# 05_FPGA_HVIO.net
KiCad netlist of a schematic drawn in Altium Designer
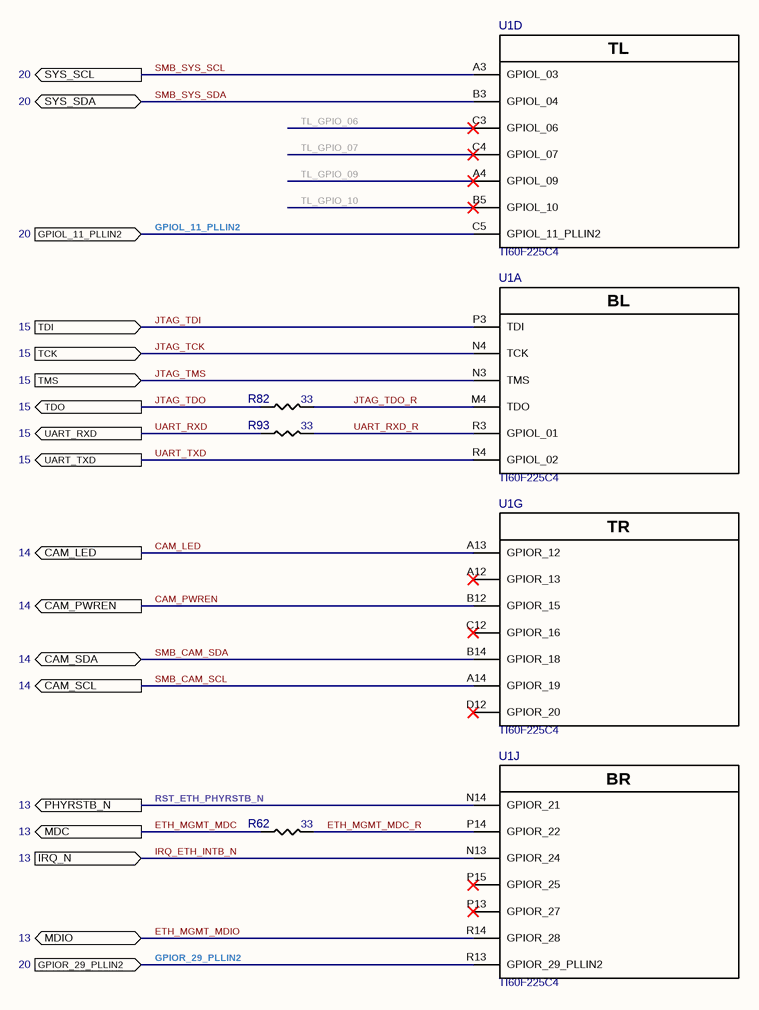
[diagram p0: 05_FPGA_HVIO.SchDoc]

(export (version "E")
  (design (tool "Eeschema 10.0.6"))
  (components
    (comp (ref "R62")
      (value "33")
      (footprint "RESC1005X03N")
      (description "RES SMD 33 OHM 1% 1/16W 0402")
      (fields (field (name "PART NUMBER") "RC0402FR-0733RL"))
      (libsource (lib "Database") (part "Resistor_ENG"))
    )
    (comp (ref "R82")
      (value "33")
      (footprint "RESC1005X03N")
      (description "RES SMD 33 OHM 1% 1/16W 0402")
      (fields (field (name "PART NUMBER") "RC0402FR-0733RL"))
      (libsource (lib "Database") (part "Resistor_ENG"))
    )
    (comp (ref "R93")
      (value "33")
      (footprint "RESC1005X03N")
      (description "RES SMD 33 OHM 1% 1/16W 0402")
      (fields (field (name "PART NUMBER") "RC0402FR-0733RL"))
      (libsource (lib "Database") (part "Resistor_ENG"))
    )
    (comp (ref "U1")
      (value "TI60F225C4")
      (footprint "BGA225C65P15X15_1000X1000X100")
      (description "FPGA TITAN 140HSIO 4PLL 225BGA")
      (libsource (lib "Database") (part "TI60F225"))
    )
  )
  (nets
    (net (code "1") (name "/CAM_LED") (class "Default")
      (node (ref "U1") (pin "A13") (pinfunction "GPIOR_12_A13") (pintype "passive"))
    )
    (net (code "2") (name "/CAM_PWREN") (class "Default")
      (node (ref "U1") (pin "B12") (pinfunction "GPIOR_15_B12") (pintype "passive"))
    )
    (net (code "3") (name "/ETH_MGMT_MDC") (class "Default")
      (node (ref "R62") (pin "1") (pinfunction "1_1") (pintype "passive"))
    )
    (net (code "4") (name "/ETH_MGMT_MDC_R") (class "Default")
      (node (ref "R62") (pin "2") (pinfunction "2_2") (pintype "passive"))
      (node (ref "U1") (pin "P14") (pinfunction "GPIOR_22_P14") (pintype "passive"))
    )
    (net (code "5") (name "/ETH_MGMT_MDIO") (class "Default")
      (node (ref "U1") (pin "R14") (pinfunction "GPIOR_28_R14") (pintype "passive"))
    )
    (net (code "6") (name "/GPIOL_11_PLLIN2") (class "Default")
      (node (ref "U1") (pin "C5") (pinfunction "GPIOL_11_PLLIN2_C5") (pintype "passive"))
    )
    (net (code "7") (name "/GPIOR_29_PLLIN2") (class "Default")
      (node (ref "U1") (pin "R13") (pinfunction "GPIOR_29_PLLIN2_R13") (pintype "passive"))
    )
    (net (code "8") (name "/IRQ_ETH_INTB_N") (class "Default")
      (node (ref "U1") (pin "N13") (pinfunction "GPIOR_24_N13") (pintype "passive"))
    )
    (net (code "9") (name "/JTAG_TCK") (class "Default")
      (node (ref "U1") (pin "N4") (pinfunction "TCK_N4") (pintype "passive"))
    )
    (net (code "10") (name "/JTAG_TDI") (class "Default")
      (node (ref "U1") (pin "P3") (pinfunction "TDI_P3") (pintype "passive"))
    )
    (net (code "11") (name "/JTAG_TDO") (class "Default")
      (node (ref "R82") (pin "1") (pinfunction "1_1") (pintype "passive"))
    )
    (net (code "12") (name "/JTAG_TDO_R") (class "Default")
      (node (ref "R82") (pin "2") (pinfunction "2_2") (pintype "passive"))
      (node (ref "U1") (pin "M4") (pinfunction "TDO_M4") (pintype "passive"))
    )
    (net (code "13") (name "/JTAG_TMS") (class "Default")
      (node (ref "U1") (pin "N3") (pinfunction "TMS_N3") (pintype "passive"))
    )
    (net (code "14") (name "/RST_ETH_PHYRSTB_N") (class "Default")
      (node (ref "U1") (pin "N14") (pinfunction "GPIOR_21_N14") (pintype "passive"))
    )
    (net (code "15") (name "/SMB_CAM_SCL") (class "Default")
      (node (ref "U1") (pin "A14") (pinfunction "GPIOR_19_A14") (pintype "passive"))
    )
    (net (code "16") (name "/SMB_CAM_SDA") (class "Default")
      (node (ref "U1") (pin "B14") (pinfunction "GPIOR_18_B14") (pintype "passive"))
    )
    (net (code "17") (name "/SMB_SYS_SCL") (class "Default")
      (node (ref "U1") (pin "A3") (pinfunction "GPIOL_03_A3") (pintype "passive"))
    )
    (net (code "18") (name "/SMB_SYS_SDA") (class "Default")
      (node (ref "U1") (pin "B3") (pinfunction "GPIOL_04_B3") (pintype "passive"))
    )
    (net (code "19") (name "/TL_GPIO_06") (class "Default")
      (node (ref "U1") (pin "C3") (pinfunction "GPIOL_06_C3") (pintype "passive+no_connect"))
    )
    (net (code "20") (name "/TL_GPIO_07") (class "Default")
      (node (ref "U1") (pin "C4") (pinfunction "GPIOL_07_C4") (pintype "passive+no_connect"))
    )
    (net (code "21") (name "/TL_GPIO_09") (class "Default")
      (node (ref "U1") (pin "A4") (pinfunction "GPIOL_09_A4") (pintype "passive+no_connect"))
    )
    (net (code "22") (name "/TL_GPIO_10") (class "Default")
      (node (ref "U1") (pin "B5") (pinfunction "GPIOL_10_B5") (pintype "passive+no_connect"))
    )
    (net (code "23") (name "/UART_RXD") (class "Default")
      (node (ref "R93") (pin "1") (pinfunction "1_1") (pintype "passive"))
    )
    (net (code "24") (name "/UART_RXD_R") (class "Default")
      (node (ref "R93") (pin "2") (pinfunction "2_2") (pintype "passive"))
      (node (ref "U1") (pin "R3") (pinfunction "GPIOL_01_R3") (pintype "passive"))
    )
    (net (code "25") (name "/UART_TXD") (class "Default")
      (node (ref "U1") (pin "R4") (pinfunction "GPIOL_02_R4") (pintype "passive"))
    )
    (net (code "26") (name "unconnected-(U1G-GPIOR_13-PadA12)") (class "Default")
      (node (ref "U1") (pin "A12") (pinfunction "GPIOR_13_A12") (pintype "passive+no_connect"))
    )
    (net (code "27") (name "unconnected-(U1G-GPIOR_16-PadC12)") (class "Default")
      (node (ref "U1") (pin "C12") (pinfunction "GPIOR_16_C12") (pintype "passive+no_connect"))
    )
    (net (code "28") (name "unconnected-(U1G-GPIOR_20-PadD12)") (class "Default")
      (node (ref "U1") (pin "D12") (pinfunction "GPIOR_20_D12") (pintype "passive+no_connect"))
    )
    (net (code "29") (name "unconnected-(U1J-GPIOR_25-PadP15)") (class "Default")
      (node (ref "U1") (pin "P15") (pinfunction "GPIOR_25_P15") (pintype "passive+no_connect"))
    )
    (net (code "30") (name "unconnected-(U1J-GPIOR_27-PadP13)") (class "Default")
      (node (ref "U1") (pin "P13") (pinfunction "GPIOR_27_P13") (pintype "passive+no_connect"))
    )
  )
)
